# KORUZA_PowerModule_v2.net
KiCad netlist of a schematic drawn in Altium Designer
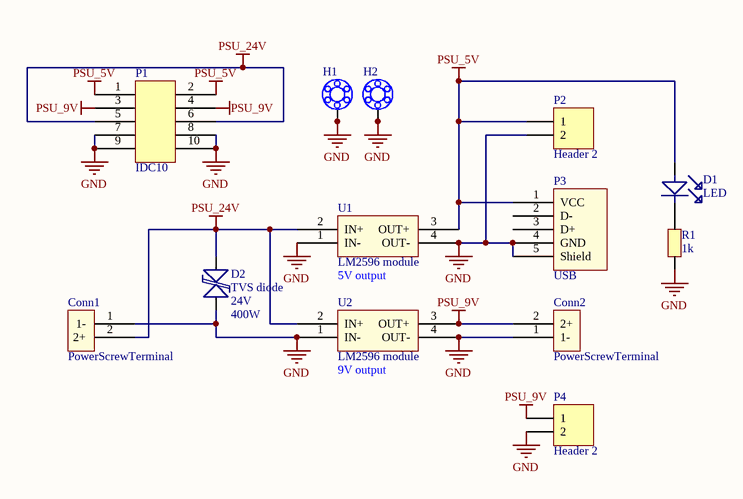
[diagram p0: KORUZA_PowerModule_v2.SchDoc]

(export (version "E")
  (design (tool "Eeschema 10.0.6"))
  (components
    (comp (ref "Conn1")
      (value "PowerScrewTerminal")
      (footprint "MKDSN 2,5/ 2-5,08")
      (libsource (lib "GeneralComponents") (part "PowerScrewTerminal"))
    )
    (comp (ref "Conn2")
      (value "PowerScrewTerminal")
      (footprint "MKDSN 2,5/ 2-5,08")
      (libsource (lib "") (part "PowerScrewTerminal_1"))
    )
    (comp (ref "D1")
      (value "LED")
      (footprint "1206/0805 diode")
      (description "LED diode")
      (libsource (lib "GeneralComponents") (part "LED"))
    )
    (comp (ref "D2")
      (value "TVS diode")
      (footprint "DIOM4750X18N")
      (description "TVS bidirectional diode")
      (fields (field (name "VOLTAGE") "24V") (field (name "POWER") "400W"))
      (libsource (lib "GeneralComponents") (part "TVS diode"))
    )
    (comp (ref "H1")
      (value "M")
      (footprint "MOUNTING")
      (description "MOUNTING HOLE - NON INSTALLABLE")
      (libsource (lib "vh_altium_library") (part "MOUNTING"))
    )
    (comp (ref "H2")
      (value "M")
      (footprint "MOUNTING")
      (description "MOUNTING HOLE - NON INSTALLABLE")
      (libsource (lib "vh_altium_library") (part "MOUNTING"))
    )
    (comp (ref "P1")
      (value "IDC10")
      (footprint "IDC10")
      (description "IDC 10pin")
      (libsource (lib "GeneralComponents") (part "IDC10"))
    )
    (comp (ref "P2")
      (value "Header 2")
      (footprint "HDR1X2")
      (description "Header, 2-Pin")
      (fields (field (name "PUBLISHER") "Altium Limited"))
      (libsource (lib "Miscellaneous Connectors") (part "Header 2"))
    )
    (comp (ref "P3")
      (value "USB")
      (footprint "USB A THT")
      (description "USB A standard receptacle")
      (libsource (lib "GeneralComponents") (part "USB"))
    )
    (comp (ref "P4")
      (value "Header 2")
      (footprint "HDR1X2")
      (description "Header, 2-Pin")
      (fields (field (name "PUBLISHER") "Altium Limited"))
      (libsource (lib "Miscellaneous Connectors") (part "Header 2"))
    )
    (comp (ref "R1")
      (value "1k")
      (footprint "RESC2012X06N")
      (description "Resistor 0805 smd")
      (libsource (lib "GeneralComponents") (part "Resistor"))
    )
    (comp (ref "U1")
      (value "LM2596 module")
      (footprint "LM2596 module")
      (libsource (lib "GeneralComponents") (part "LM2596 module"))
    )
    (comp (ref "U2")
      (value "LM2596 module")
      (footprint "LM2596 module")
      (libsource (lib "GeneralComponents") (part "LM2596 module"))
    )
  )
  (nets
    (net (code "1") (name "GND") (class "Default")
      (node (ref "Conn1") (pin "1") (pinfunction "1-_1") (pintype "passive"))
      (node (ref "Conn2") (pin "1") (pinfunction "1-_1") (pintype "passive"))
      (node (ref "D2") (pin "1") (pinfunction "1_1") (pintype "passive"))
      (node (ref "H1") (pin "1") (pinfunction "1_1") (pintype "passive"))
      (node (ref "H1") (pin "2") (pinfunction "2_2") (pintype "passive"))
      (node (ref "H1") (pin "3") (pinfunction "3_3") (pintype "passive"))
      (node (ref "H1") (pin "4") (pinfunction "4_4") (pintype "passive"))
      (node (ref "H1") (pin "5") (pinfunction "5_5") (pintype "passive"))
      (node (ref "H1") (pin "6") (pinfunction "6_6") (pintype "passive"))
      (node (ref "H1") (pin "7") (pinfunction "7_7") (pintype "passive"))
      (node (ref "H2") (pin "1") (pinfunction "1_1") (pintype "passive"))
      (node (ref "H2") (pin "2") (pinfunction "2_2") (pintype "passive"))
      (node (ref "H2") (pin "3") (pinfunction "3_3") (pintype "passive"))
      (node (ref "H2") (pin "4") (pinfunction "4_4") (pintype "passive"))
      (node (ref "H2") (pin "5") (pinfunction "5_5") (pintype "passive"))
      (node (ref "H2") (pin "6") (pinfunction "6_6") (pintype "passive"))
      (node (ref "H2") (pin "7") (pinfunction "7_7") (pintype "passive"))
      (node (ref "P1") (pin "10") (pinfunction "10_10") (pintype "passive"))
      (node (ref "P1") (pin "7") (pinfunction "7_7") (pintype "passive"))
      (node (ref "P1") (pin "8") (pinfunction "8_8") (pintype "passive"))
      (node (ref "P1") (pin "9") (pinfunction "9_9") (pintype "passive"))
      (node (ref "P2") (pin "2") (pinfunction "2_2") (pintype "passive"))
      (node (ref "P3") (pin "4") (pinfunction "GND_4") (pintype "power_in"))
      (node (ref "P3") (pin "5") (pinfunction "Shield_5") (pintype "power_in"))
      (node (ref "P4") (pin "2") (pinfunction "2_2") (pintype "passive"))
      (node (ref "R1") (pin "1") (pinfunction "1_1") (pintype "passive"))
      (node (ref "U1") (pin "1") (pinfunction "IN-_1") (pintype "passive"))
      (node (ref "U1") (pin "4") (pinfunction "OUT-_4") (pintype "passive"))
      (node (ref "U2") (pin "1") (pinfunction "IN-_1") (pintype "passive"))
      (node (ref "U2") (pin "4") (pinfunction "OUT-_4") (pintype "passive"))
    )
    (net (code "2") (name "Net-(D1-Pad2)") (class "Default")
      (node (ref "D1") (pin "2") (pinfunction "2_2") (pintype "passive"))
      (node (ref "R1") (pin "2") (pinfunction "2_2") (pintype "passive"))
    )
    (net (code "3") (name "PSU_5V") (class "Default")
      (node (ref "D1") (pin "1") (pinfunction "1_1") (pintype "passive"))
      (node (ref "P1") (pin "1") (pinfunction "A_1") (pintype "passive"))
      (node (ref "P1") (pin "2") (pinfunction "2_2") (pintype "passive"))
      (node (ref "P2") (pin "1") (pinfunction "1_1") (pintype "passive"))
      (node (ref "P3") (pin "1") (pinfunction "VCC_1") (pintype "power_in"))
      (node (ref "U1") (pin "3") (pinfunction "OUT+_3") (pintype "passive"))
    )
    (net (code "4") (name "PSU_9V") (class "Default")
      (node (ref "Conn2") (pin "2") (pinfunction "2+_2") (pintype "passive"))
      (node (ref "P1") (pin "3") (pinfunction "3_3") (pintype "passive"))
      (node (ref "P1") (pin "4") (pinfunction "4_4") (pintype "passive"))
      (node (ref "P4") (pin "1") (pinfunction "1_1") (pintype "passive"))
      (node (ref "U2") (pin "3") (pinfunction "OUT+_3") (pintype "passive"))
    )
    (net (code "5") (name "PSU_24V") (class "Default")
      (node (ref "Conn1") (pin "2") (pinfunction "2+_2") (pintype "passive"))
      (node (ref "D2") (pin "2") (pinfunction "2_2") (pintype "passive"))
      (node (ref "P1") (pin "5") (pinfunction "5_5") (pintype "passive"))
      (node (ref "P1") (pin "6") (pinfunction "6_6") (pintype "passive"))
      (node (ref "U1") (pin "2") (pinfunction "IN+_2") (pintype "passive"))
      (node (ref "U2") (pin "2") (pinfunction "IN+_2") (pintype "passive"))
    )
    (net (code "6") (name "unconnected-(P3-D+-Pad3)") (class "Default")
      (node (ref "P3") (pin "3") (pinfunction "D+_3") (pintype "power_in"))
    )
    (net (code "7") (name "unconnected-(P3-D--Pad2)") (class "Default")
      (node (ref "P3") (pin "2") (pinfunction "D-_2") (pintype "power_in"))
    )
  )
)
